# FrontEnd_SingleChannel.net
KiCad netlist of a schematic drawn in Altium Designer
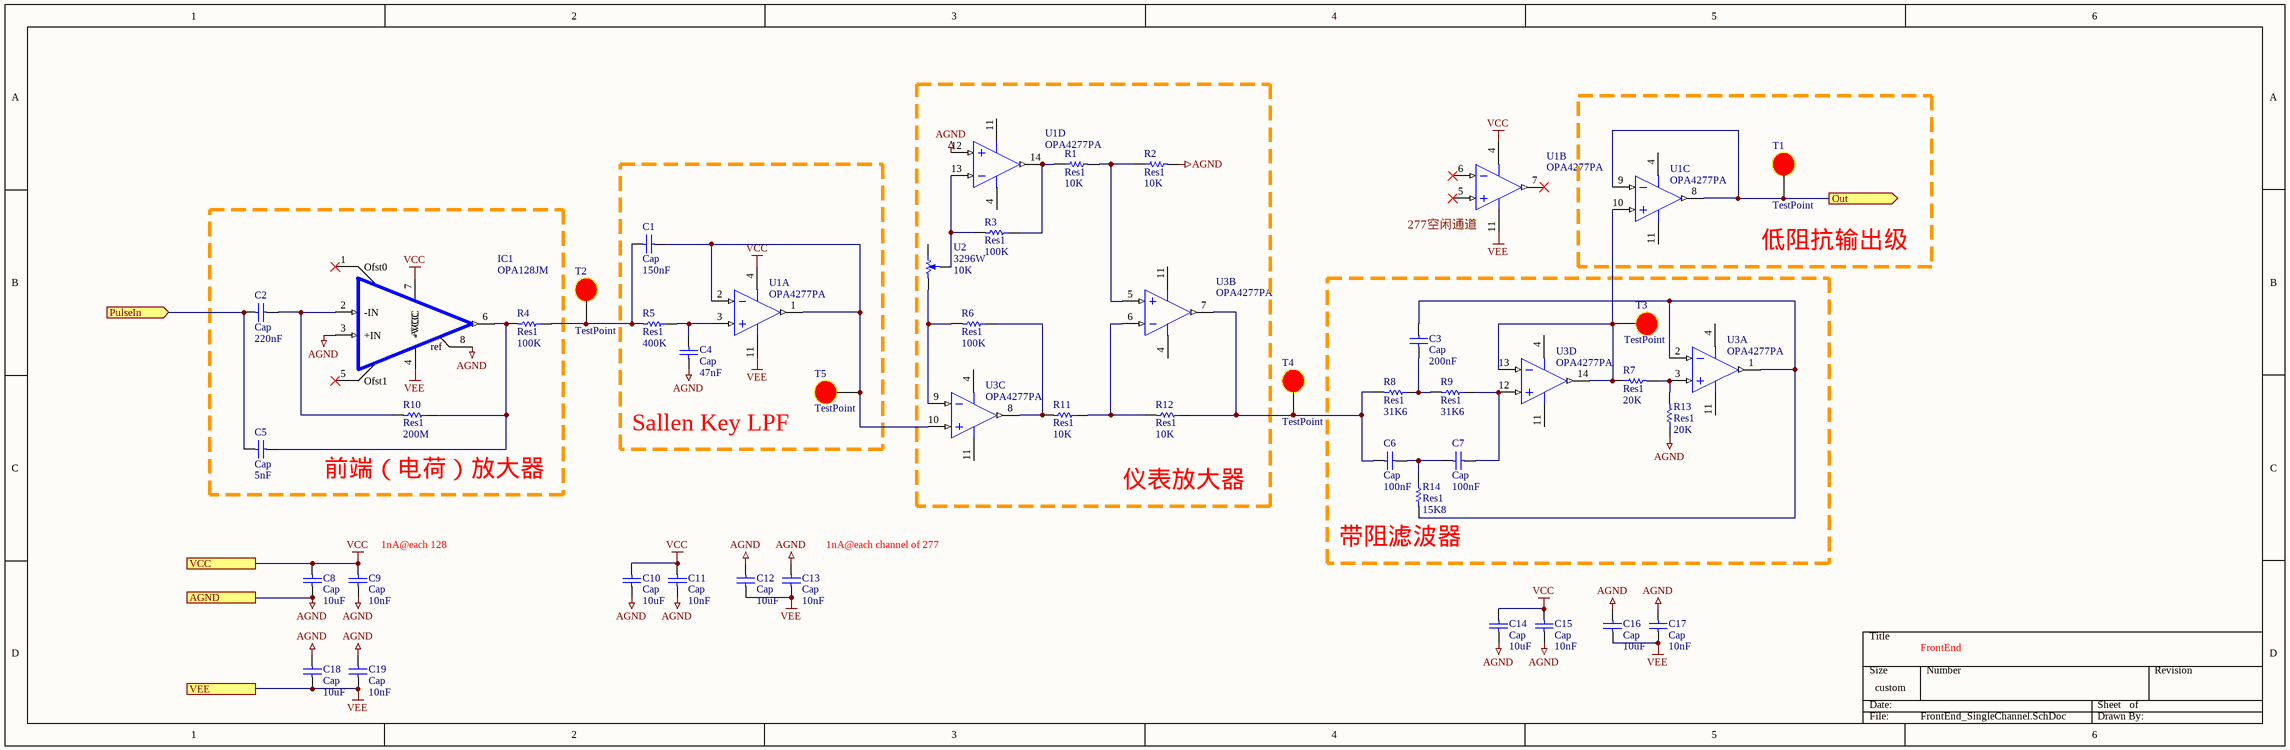
[diagram p0: FrontEnd_SingleChannel.SchDoc]

(export (version "E")
  (design (tool "Eeschema 10.0.6"))
  (components
    (comp (ref "C1")
      (value "Cap")
      (footprint "0603C")
      (description "Capacitor")
      (fields (field (name "ALTIUM_VALUE") "150nF") (field (name "PUBLISHER") "Altium Limited"))
      (libsource (lib "Miscellaneous Devices") (part "Cap"))
    )
    (comp (ref "C2")
      (value "Cap")
      (footprint "0603C")
      (description "Capacitor")
      (fields (field (name "ALTIUM_VALUE") "220nF") (field (name "PUBLISHER") "Altium Limited"))
      (libsource (lib "Miscellaneous Devices") (part "Cap"))
    )
    (comp (ref "C3")
      (value "Cap")
      (footprint "0603C")
      (description "Capacitor")
      (fields (field (name "ALTIUM_VALUE") "200nF") (field (name "PUBLISHER") "Altium Limited"))
      (libsource (lib "Miscellaneous Devices") (part "Cap"))
    )
    (comp (ref "C4")
      (value "Cap")
      (footprint "0603C")
      (description "Capacitor")
      (fields (field (name "ALTIUM_VALUE") "47nF") (field (name "PUBLISHER") "Altium Limited"))
      (libsource (lib "Miscellaneous Devices") (part "Cap"))
    )
    (comp (ref "C5")
      (value "Cap")
      (footprint "0603C")
      (description "Capacitor")
      (fields (field (name "ALTIUM_VALUE") "5nF") (field (name "PUBLISHER") "Altium Limited"))
      (libsource (lib "Miscellaneous Devices") (part "Cap"))
    )
    (comp (ref "C6")
      (value "Cap")
      (footprint "0603C")
      (description "Capacitor")
      (fields (field (name "ALTIUM_VALUE") "100nF") (field (name "PUBLISHER") "Altium Limited"))
      (libsource (lib "Miscellaneous Devices") (part "Cap"))
    )
    (comp (ref "C7")
      (value "Cap")
      (footprint "0603C")
      (description "Capacitor")
      (fields (field (name "ALTIUM_VALUE") "100nF") (field (name "PUBLISHER") "Altium Limited"))
      (libsource (lib "Miscellaneous Devices") (part "Cap"))
    )
    (comp (ref "C8")
      (value "Cap")
      (footprint "0603C")
      (description "Capacitor")
      (fields (field (name "ALTIUM_VALUE") "10uF") (field (name "PUBLISHER") "Altium Limited"))
      (libsource (lib "Miscellaneous Devices") (part "Cap"))
    )
    (comp (ref "C9")
      (value "Cap")
      (footprint "0603C")
      (description "Capacitor")
      (fields (field (name "ALTIUM_VALUE") "10nF") (field (name "PUBLISHER") "Altium Limited"))
      (libsource (lib "Miscellaneous Devices") (part "Cap"))
    )
    (comp (ref "C10")
      (value "Cap")
      (footprint "0603C")
      (description "Capacitor")
      (fields (field (name "ALTIUM_VALUE") "10uF") (field (name "PUBLISHER") "Altium Limited"))
      (libsource (lib "Miscellaneous Devices") (part "Cap"))
    )
    (comp (ref "C11")
      (value "Cap")
      (footprint "0603C")
      (description "Capacitor")
      (fields (field (name "ALTIUM_VALUE") "10nF") (field (name "PUBLISHER") "Altium Limited"))
      (libsource (lib "Miscellaneous Devices") (part "Cap"))
    )
    (comp (ref "C12")
      (value "Cap")
      (footprint "0603C")
      (description "Capacitor")
      (fields (field (name "ALTIUM_VALUE") "10uF") (field (name "PUBLISHER") "Altium Limited"))
      (libsource (lib "Miscellaneous Devices") (part "Cap"))
    )
    (comp (ref "C13")
      (value "Cap")
      (footprint "0603C")
      (description "Capacitor")
      (fields (field (name "ALTIUM_VALUE") "10nF") (field (name "PUBLISHER") "Altium Limited"))
      (libsource (lib "Miscellaneous Devices") (part "Cap"))
    )
    (comp (ref "C14")
      (value "Cap")
      (footprint "0603C")
      (description "Capacitor")
      (fields (field (name "ALTIUM_VALUE") "10uF") (field (name "PUBLISHER") "Altium Limited"))
      (libsource (lib "Miscellaneous Devices") (part "Cap"))
    )
    (comp (ref "C15")
      (value "Cap")
      (footprint "0603C")
      (description "Capacitor")
      (fields (field (name "ALTIUM_VALUE") "10nF") (field (name "PUBLISHER") "Altium Limited"))
      (libsource (lib "Miscellaneous Devices") (part "Cap"))
    )
    (comp (ref "C16")
      (value "Cap")
      (footprint "0603C")
      (description "Capacitor")
      (fields (field (name "ALTIUM_VALUE") "10uF") (field (name "PUBLISHER") "Altium Limited"))
      (libsource (lib "Miscellaneous Devices") (part "Cap"))
    )
    (comp (ref "C17")
      (value "Cap")
      (footprint "0603C")
      (description "Capacitor")
      (fields (field (name "ALTIUM_VALUE") "10nF") (field (name "PUBLISHER") "Altium Limited"))
      (libsource (lib "Miscellaneous Devices") (part "Cap"))
    )
    (comp (ref "C18")
      (value "Cap")
      (footprint "0603C")
      (description "Capacitor")
      (fields (field (name "ALTIUM_VALUE") "10uF") (field (name "PUBLISHER") "Altium Limited"))
      (libsource (lib "Miscellaneous Devices") (part "Cap"))
    )
    (comp (ref "C19")
      (value "Cap")
      (footprint "0603C")
      (description "Capacitor")
      (fields (field (name "ALTIUM_VALUE") "10nF") (field (name "PUBLISHER") "Altium Limited"))
      (libsource (lib "Miscellaneous Devices") (part "Cap"))
    )
    (comp (ref "IC1")
      (value "OPA128JM")
      (footprint "脉诊:OPT301M")
      (description "电荷放大器")
      (fields
        (field (name "MANUFACTURER_PART_NUMBER") "OPA128LM")
        (field (name "MOUSER PART NUMBER") "595-OPA128LM")
      )
      (libsource (lib "脉诊") (part "OPA128JM"))
    )
    (comp (ref "R1")
      (value "Res1")
      (footprint "0603R")
      (description "Resistor")
      (fields (field (name "ALTIUM_VALUE") "10K") (field (name "PUBLISHER") "Altium Limited"))
      (libsource (lib "Miscellaneous Devices") (part "Res1"))
    )
    (comp (ref "R2")
      (value "Res1")
      (footprint "0603R")
      (description "Resistor")
      (fields (field (name "ALTIUM_VALUE") "10K") (field (name "PUBLISHER") "Altium Limited"))
      (libsource (lib "Miscellaneous Devices") (part "Res1"))
    )
    (comp (ref "R3")
      (value "Res1")
      (footprint "0603R")
      (description "Resistor")
      (fields (field (name "ALTIUM_VALUE") "100K") (field (name "PUBLISHER") "Altium Limited"))
      (libsource (lib "Miscellaneous Devices") (part "Res1"))
    )
    (comp (ref "R4")
      (value "Res1")
      (footprint "0603R")
      (description "Resistor")
      (fields (field (name "ALTIUM_VALUE") "100K") (field (name "PUBLISHER") "Altium Limited"))
      (libsource (lib "Miscellaneous Devices") (part "Res1"))
    )
    (comp (ref "R5")
      (value "Res1")
      (footprint "0603R")
      (description "Resistor")
      (fields (field (name "ALTIUM_VALUE") "400K") (field (name "PUBLISHER") "Altium Limited"))
      (libsource (lib "Miscellaneous Devices") (part "Res1"))
    )
    (comp (ref "R6")
      (value "Res1")
      (footprint "0603R")
      (description "Resistor")
      (fields (field (name "ALTIUM_VALUE") "100K") (field (name "PUBLISHER") "Altium Limited"))
      (libsource (lib "Miscellaneous Devices") (part "Res1"))
    )
    (comp (ref "R7")
      (value "Res1")
      (footprint "0603R")
      (description "Resistor")
      (fields (field (name "ALTIUM_VALUE") "20K") (field (name "PUBLISHER") "Altium Limited"))
      (libsource (lib "Miscellaneous Devices") (part "Res1"))
    )
    (comp (ref "R8")
      (value "Res1")
      (footprint "0603R")
      (description "Resistor")
      (fields (field (name "ALTIUM_VALUE") "31K6") (field (name "PUBLISHER") "Altium Limited"))
      (libsource (lib "Miscellaneous Devices") (part "Res1"))
    )
    (comp (ref "R9")
      (value "Res1")
      (footprint "0603R")
      (description "Resistor")
      (fields (field (name "ALTIUM_VALUE") "31K6") (field (name "PUBLISHER") "Altium Limited"))
      (libsource (lib "Miscellaneous Devices") (part "Res1"))
    )
    (comp (ref "R10")
      (value "Res1")
      (footprint "0603R")
      (description "Resistor")
      (fields (field (name "ALTIUM_VALUE") "200M") (field (name "PUBLISHER") "Altium Limited"))
      (libsource (lib "Miscellaneous Devices") (part "Res1"))
    )
    (comp (ref "R11")
      (value "Res1")
      (footprint "0603R")
      (description "Resistor")
      (fields (field (name "ALTIUM_VALUE") "10K") (field (name "PUBLISHER") "Altium Limited"))
      (libsource (lib "Miscellaneous Devices") (part "Res1"))
    )
    (comp (ref "R12")
      (value "Res1")
      (footprint "0603R")
      (description "Resistor")
      (fields (field (name "ALTIUM_VALUE") "10K") (field (name "PUBLISHER") "Altium Limited"))
      (libsource (lib "Miscellaneous Devices") (part "Res1"))
    )
    (comp (ref "R13")
      (value "Res1")
      (footprint "0603R")
      (description "Resistor")
      (fields (field (name "ALTIUM_VALUE") "20K") (field (name "PUBLISHER") "Altium Limited"))
      (libsource (lib "Miscellaneous Devices") (part "Res1"))
    )
    (comp (ref "R14")
      (value "Res1")
      (footprint "0603R")
      (description "Resistor")
      (fields (field (name "ALTIUM_VALUE") "15K8") (field (name "PUBLISHER") "Altium Limited"))
      (libsource (lib "Miscellaneous Devices") (part "Res1"))
    )
    (comp (ref "T1")
      (value "TestPoint")
      (footprint "TP_D1mm")
      (description "测试点")
      (libsource (lib "脉诊") (part "TP"))
    )
    (comp (ref "T2")
      (value "TestPoint")
      (footprint "TP_D1mm")
      (description "测试点")
      (libsource (lib "脉诊") (part "TP"))
    )
    (comp (ref "T3")
      (value "TestPoint")
      (footprint "TP_D1mm")
      (description "测试点")
      (libsource (lib "脉诊") (part "TP"))
    )
    (comp (ref "T4")
      (value "TestPoint")
      (footprint "TP_D1mm")
      (description "测试点")
      (libsource (lib "脉诊") (part "TP"))
    )
    (comp (ref "T5")
      (value "TestPoint")
      (footprint "TP_D1mm")
      (description "测试点")
      (libsource (lib "脉诊") (part "TP"))
    )
    (comp (ref "U1")
      (value "OPA4277PA")
      (footprint "TI-N14")
      (fields (field (name "MANUFACTURER") "Texas Instruments"))
      (libsource (lib "TI Amplifiers and Linear Operational Amplifier Precision Amplifier Part One") (part "OPA4277PA"))
    )
    (comp (ref "U2")
      (value "3296W")
      (footprint "POT4MM-2")
      (description "Square Trimming Potentiometer")
      (fields (field (name "FULLVALUE") "10K") (field (name "PUBLISHER") "Altium Limited"))
      (libsource (lib "Miscellaneous Devices") (part "RPot SM"))
    )
    (comp (ref "U3")
      (value "OPA4277PA")
      (footprint "TI-N14")
      (fields (field (name "MANUFACTURER") "Texas Instruments"))
      (libsource (lib "TI Amplifiers and Linear Operational Amplifier Precision Amplifier Part One") (part "OPA4277PA"))
    )
  )
  (nets
    (net (code "1") (name "/Out") (class "Default")
      (node (ref "T1") (pin "9") (pinfunction "1_9") (pintype "passive"))
      (node (ref "U1") (pin "8") (pinfunction "OUT_C_8") (pintype "output"))
      (node (ref "U1") (pin "9") (pinfunction "IN_C-_9") (pintype "input"))
    )
    (net (code "2") (name "/PulseIn") (class "Default")
      (node (ref "C2") (pin "1") (pinfunction "1_1") (pintype "passive"))
      (node (ref "C5") (pin "1") (pinfunction "1_1") (pintype "passive"))
    )
    (net (code "3") (name "AGND") (class "Default")
      (node (ref "C10") (pin "1") (pinfunction "1_1") (pintype "passive"))
      (node (ref "C11") (pin "1") (pinfunction "1_1") (pintype "passive"))
      (node (ref "C12") (pin "1") (pinfunction "1_1") (pintype "passive"))
      (node (ref "C13") (pin "1") (pinfunction "1_1") (pintype "passive"))
      (node (ref "C14") (pin "1") (pinfunction "1_1") (pintype "passive"))
      (node (ref "C15") (pin "1") (pinfunction "1_1") (pintype "passive"))
      (node (ref "C16") (pin "1") (pinfunction "1_1") (pintype "passive"))
      (node (ref "C17") (pin "1") (pinfunction "1_1") (pintype "passive"))
      (node (ref "C18") (pin "1") (pinfunction "1_1") (pintype "passive"))
      (node (ref "C19") (pin "1") (pinfunction "1_1") (pintype "passive"))
      (node (ref "C4") (pin "1") (pinfunction "1_1") (pintype "passive"))
      (node (ref "C8") (pin "1") (pinfunction "1_1") (pintype "passive"))
      (node (ref "C9") (pin "1") (pinfunction "1_1") (pintype "passive"))
      (node (ref "IC1") (pin "3") (pinfunction "+IN_3") (pintype "input"))
      (node (ref "IC1") (pin "8") (pinfunction "ref_8") (pintype "passive"))
      (node (ref "R13") (pin "1") (pinfunction "1_1") (pintype "passive"))
      (node (ref "R2") (pin "2") (pinfunction "2_2") (pintype "passive"))
      (node (ref "U1") (pin "12") (pinfunction "IN_D+_12") (pintype "input"))
    )
    (net (code "4") (name "Net-(C3-Pad2)") (class "Default")
      (node (ref "C3") (pin "2") (pinfunction "2_2") (pintype "passive"))
      (node (ref "R8") (pin "1") (pinfunction "1_1") (pintype "passive"))
      (node (ref "R9") (pin "2") (pinfunction "2_2") (pintype "passive"))
    )
    (net (code "5") (name "Net-(C6-Pad2)") (class "Default")
      (node (ref "C6") (pin "2") (pinfunction "2_2") (pintype "passive"))
      (node (ref "C7") (pin "1") (pinfunction "1_1") (pintype "passive"))
      (node (ref "R14") (pin "1") (pinfunction "1_1") (pintype "passive"))
    )
    (net (code "6") (name "Net-(IC1--IN)") (class "Default")
      (node (ref "C2") (pin "2") (pinfunction "2_2") (pintype "passive"))
      (node (ref "IC1") (pin "2") (pinfunction "-IN_2") (pintype "input"))
      (node (ref "R10") (pin "2") (pinfunction "2_2") (pintype "passive"))
    )
    (net (code "7") (name "Net-(IC1-OUT)") (class "Default")
      (node (ref "C5") (pin "2") (pinfunction "2_2") (pintype "passive"))
      (node (ref "IC1") (pin "6") (pinfunction "OUT_6") (pintype "output"))
      (node (ref "R10") (pin "1") (pinfunction "1_1") (pintype "passive"))
      (node (ref "R4") (pin "2") (pinfunction "2_2") (pintype "passive"))
    )
    (net (code "8") (name "Net-(T2-1)") (class "Default")
      (node (ref "C1") (pin "1") (pinfunction "1_1") (pintype "passive"))
      (node (ref "R4") (pin "1") (pinfunction "1_1") (pintype "passive"))
      (node (ref "R5") (pin "2") (pinfunction "2_2") (pintype "passive"))
      (node (ref "T2") (pin "9") (pinfunction "1_9") (pintype "passive"))
    )
    (net (code "9") (name "Net-(T3-1)") (class "Default")
      (node (ref "R7") (pin "1") (pinfunction "1_1") (pintype "passive"))
      (node (ref "T3") (pin "9") (pinfunction "1_9") (pintype "passive"))
      (node (ref "U1") (pin "10") (pinfunction "IN_C+_10") (pintype "input"))
      (node (ref "U3") (pin "13") (pinfunction "IN_D-_13") (pintype "input"))
      (node (ref "U3") (pin "14") (pinfunction "OUT_D_14") (pintype "output"))
    )
    (net (code "10") (name "Net-(T4-1)") (class "Default")
      (node (ref "C6") (pin "1") (pinfunction "1_1") (pintype "passive"))
      (node (ref "R12") (pin "1") (pinfunction "1_1") (pintype "passive"))
      (node (ref "R8") (pin "2") (pinfunction "2_2") (pintype "passive"))
      (node (ref "T4") (pin "9") (pinfunction "1_9") (pintype "passive"))
      (node (ref "U3") (pin "7") (pinfunction "OUT_B_7") (pintype "output"))
    )
    (net (code "11") (name "Net-(T5-1)") (class "Default")
      (node (ref "C1") (pin "2") (pinfunction "2_2") (pintype "passive"))
      (node (ref "T5") (pin "9") (pinfunction "1_9") (pintype "passive"))
      (node (ref "U1") (pin "1") (pinfunction "OUT_A_1") (pintype "output"))
      (node (ref "U1") (pin "2") (pinfunction "IN_A-_2") (pintype "input"))
      (node (ref "U3") (pin "10") (pinfunction "IN_C+_10") (pintype "input"))
    )
    (net (code "12") (name "Net-(U1A-IN_A+)") (class "Default")
      (node (ref "C4") (pin "2") (pinfunction "2_2") (pintype "passive"))
      (node (ref "R5") (pin "1") (pinfunction "1_1") (pintype "passive"))
      (node (ref "U1") (pin "3") (pinfunction "IN_A+_3") (pintype "input"))
    )
    (net (code "13") (name "Net-(U1D-IN_D-)") (class "Default")
      (node (ref "R3") (pin "2") (pinfunction "2_2") (pintype "passive"))
      (node (ref "U1") (pin "13") (pinfunction "IN_D-_13") (pintype "input"))
      (node (ref "U2") (pin "W") (pinfunction "W_W") (pintype "passive"))
    )
    (net (code "14") (name "Net-(U1D-OUT_D)") (class "Default")
      (node (ref "R1") (pin "1") (pinfunction "1_1") (pintype "passive"))
      (node (ref "R3") (pin "1") (pinfunction "1_1") (pintype "passive"))
      (node (ref "U1") (pin "14") (pinfunction "OUT_D_14") (pintype "output"))
    )
    (net (code "15") (name "Net-(U2--)") (class "Default")
      (node (ref "R6") (pin "2") (pinfunction "2_2") (pintype "passive"))
      (node (ref "U2") (pin "CCW") (pinfunction "-_CCW") (pintype "passive"))
      (node (ref "U3") (pin "9") (pinfunction "IN_C-_9") (pintype "input"))
    )
    (net (code "16") (name "Net-(U3A-IN_A+)") (class "Default")
      (node (ref "R13") (pin "2") (pinfunction "2_2") (pintype "passive"))
      (node (ref "R7") (pin "2") (pinfunction "2_2") (pintype "passive"))
      (node (ref "U3") (pin "3") (pinfunction "IN_A+_3") (pintype "input"))
    )
    (net (code "17") (name "Net-(U3A-IN_A-)") (class "Default")
      (node (ref "C3") (pin "1") (pinfunction "1_1") (pintype "passive"))
      (node (ref "R14") (pin "2") (pinfunction "2_2") (pintype "passive"))
      (node (ref "U3") (pin "1") (pinfunction "OUT_A_1") (pintype "output"))
      (node (ref "U3") (pin "2") (pinfunction "IN_A-_2") (pintype "input"))
    )
    (net (code "18") (name "Net-(U3B-IN_B+)") (class "Default")
      (node (ref "R1") (pin "2") (pinfunction "2_2") (pintype "passive"))
      (node (ref "R2") (pin "1") (pinfunction "1_1") (pintype "passive"))
      (node (ref "U3") (pin "5") (pinfunction "IN_B+_5") (pintype "input"))
    )
    (net (code "19") (name "Net-(U3B-IN_B-)") (class "Default")
      (node (ref "R11") (pin "1") (pinfunction "1_1") (pintype "passive"))
      (node (ref "R12") (pin "2") (pinfunction "2_2") (pintype "passive"))
      (node (ref "U3") (pin "6") (pinfunction "IN_B-_6") (pintype "input"))
    )
    (net (code "20") (name "Net-(U3C-OUT_C)") (class "Default")
      (node (ref "R11") (pin "2") (pinfunction "2_2") (pintype "passive"))
      (node (ref "R6") (pin "1") (pinfunction "1_1") (pintype "passive"))
      (node (ref "U3") (pin "8") (pinfunction "OUT_C_8") (pintype "output"))
    )
    (net (code "21") (name "Net-(U3D-IN_D+)") (class "Default")
      (node (ref "C7") (pin "2") (pinfunction "2_2") (pintype "passive"))
      (node (ref "R9") (pin "1") (pinfunction "1_1") (pintype "passive"))
      (node (ref "U3") (pin "12") (pinfunction "IN_D+_12") (pintype "input"))
    )
    (net (code "22") (name "VCC") (class "Default")
      (node (ref "C10") (pin "2") (pinfunction "2_2") (pintype "passive"))
      (node (ref "C11") (pin "2") (pinfunction "2_2") (pintype "passive"))
      (node (ref "C14") (pin "2") (pinfunction "2_2") (pintype "passive"))
      (node (ref "C15") (pin "2") (pinfunction "2_2") (pintype "passive"))
      (node (ref "C8") (pin "2") (pinfunction "2_2") (pintype "passive"))
      (node (ref "C9") (pin "2") (pinfunction "2_2") (pintype "passive"))
      (node (ref "IC1") (pin "7") (pinfunction "+VCC_7") (pintype "power_in"))
      (node (ref "U1") (pin "4") (pinfunction "V+_4") (pintype "power_in"))
    )
    (net (code "23") (name "VEE") (class "Default")
      (node (ref "C12") (pin "2") (pinfunction "2_2") (pintype "passive"))
      (node (ref "C13") (pin "2") (pinfunction "2_2") (pintype "passive"))
      (node (ref "C16") (pin "2") (pinfunction "2_2") (pintype "passive"))
      (node (ref "C17") (pin "2") (pinfunction "2_2") (pintype "passive"))
      (node (ref "C18") (pin "2") (pinfunction "2_2") (pintype "passive"))
      (node (ref "C19") (pin "2") (pinfunction "2_2") (pintype "passive"))
      (node (ref "IC1") (pin "4") (pinfunction "-VCC_4") (pintype "power_in"))
      (node (ref "U1") (pin "11") (pinfunction "V-_11") (pintype "power_in"))
    )
    (net (code "24") (name "unconnected-(IC1-Ofst0-Pad1)") (class "Default")
      (node (ref "IC1") (pin "1") (pinfunction "Ofst0_1") (pintype "passive+no_connect"))
    )
    (net (code "25") (name "unconnected-(IC1-Ofst1-Pad5)") (class "Default")
      (node (ref "IC1") (pin "5") (pinfunction "Ofst1_5") (pintype "passive+no_connect"))
    )
    (net (code "26") (name "unconnected-(U1B-IN_B+-Pad5)") (class "Default")
      (node (ref "U1") (pin "5") (pinfunction "IN_B+_5") (pintype "input+no_connect"))
    )
    (net (code "27") (name "unconnected-(U1B-IN_B--Pad6)") (class "Default")
      (node (ref "U1") (pin "6") (pinfunction "IN_B-_6") (pintype "input+no_connect"))
    )
    (net (code "28") (name "unconnected-(U1B-OUT_B-Pad7)") (class "Default")
      (node (ref "U1") (pin "7") (pinfunction "OUT_B_7") (pintype "output+no_connect"))
    )
    (net (code "29") (name "unconnected-(U1C-V+-Pad4)") (class "Default")
      (node (ref "U1") (pin "4") (pinfunction "V+_4") (pintype "power_in"))
    )
    (net (code "30") (name "unconnected-(U1C-V--Pad11)") (class "Default")
      (node (ref "U1") (pin "11") (pinfunction "V-_11") (pintype "power_in"))
    )
    (net (code "31") (name "unconnected-(U1D-V+-Pad4)") (class "Default")
      (node (ref "U1") (pin "4") (pinfunction "V+_4") (pintype "power_in"))
    )
    (net (code "32") (name "unconnected-(U1D-V--Pad11)") (class "Default")
      (node (ref "U1") (pin "11") (pinfunction "V-_11") (pintype "power_in"))
    )
    (net (code "33") (name "unconnected-(U2-+-PadCW)") (class "Default")
      (node (ref "U2") (pin "CW") (pinfunction "+_CW") (pintype "passive"))
    )
    (net (code "34") (name "unconnected-(U3A-V+-Pad4)") (class "Default")
      (node (ref "U3") (pin "4") (pinfunction "V+_4") (pintype "power_in"))
    )
    (net (code "35") (name "unconnected-(U3A-V--Pad11)") (class "Default")
      (node (ref "U3") (pin "11") (pinfunction "V-_11") (pintype "power_in"))
    )
    (net (code "36") (name "unconnected-(U3B-V+-Pad4)") (class "Default")
      (node (ref "U3") (pin "4") (pinfunction "V+_4") (pintype "power_in"))
    )
    (net (code "37") (name "unconnected-(U3B-V--Pad11)") (class "Default")
      (node (ref "U3") (pin "11") (pinfunction "V-_11") (pintype "power_in"))
    )
    (net (code "38") (name "unconnected-(U3C-V+-Pad4)") (class "Default")
      (node (ref "U3") (pin "4") (pinfunction "V+_4") (pintype "power_in"))
    )
    (net (code "39") (name "unconnected-(U3C-V--Pad11)") (class "Default")
      (node (ref "U3") (pin "11") (pinfunction "V-_11") (pintype "power_in"))
    )
    (net (code "40") (name "unconnected-(U3D-V+-Pad4)") (class "Default")
      (node (ref "U3") (pin "4") (pinfunction "V+_4") (pintype "power_in"))
    )
    (net (code "41") (name "unconnected-(U3D-V--Pad11)") (class "Default")
      (node (ref "U3") (pin "11") (pinfunction "V-_11") (pintype "power_in"))
    )
  )
)
